# NMEA2000-FluidLevel.net
KiCad netlist of a schematic drawn in EAGLE
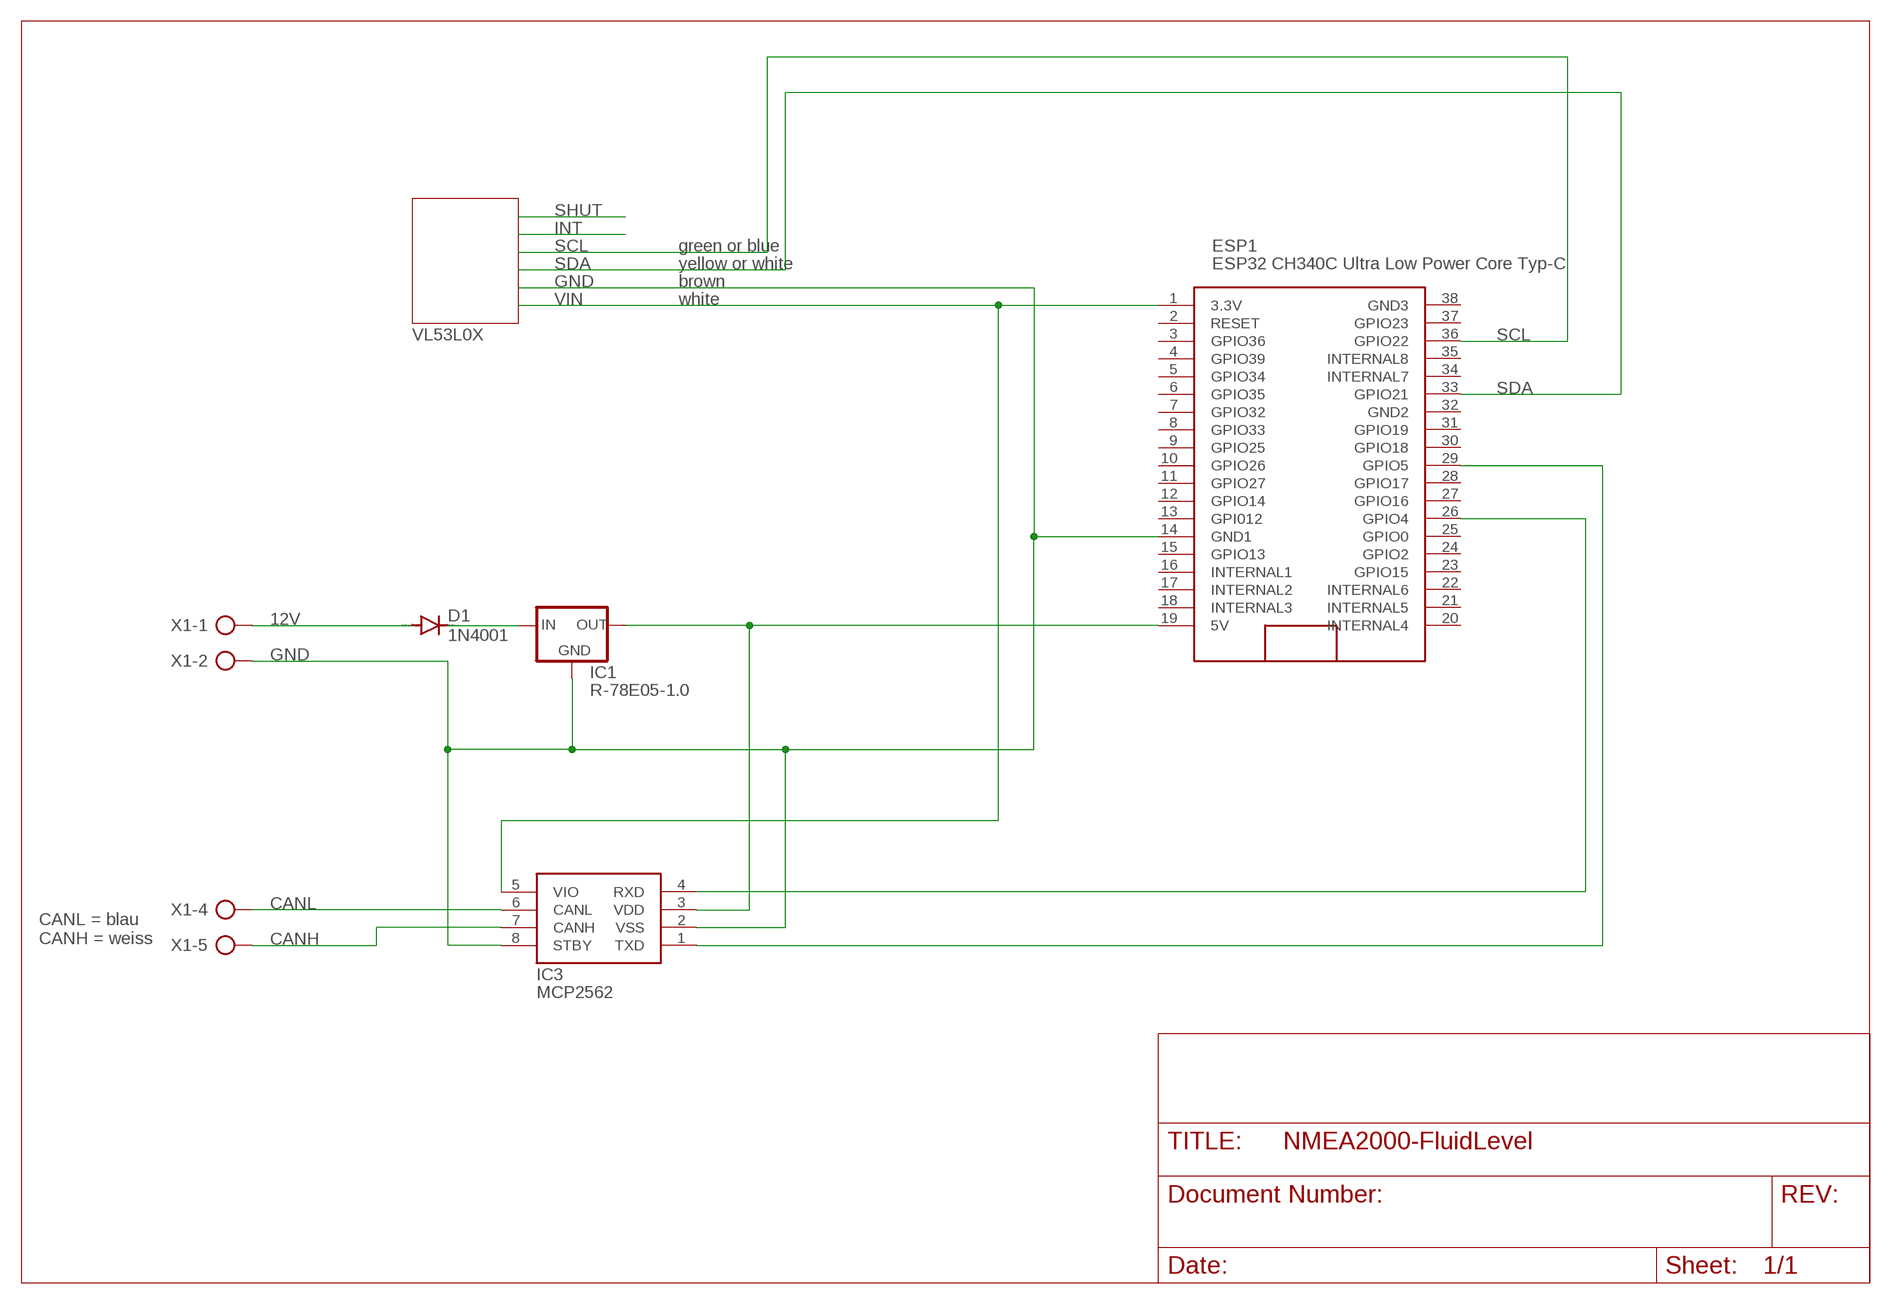
[diagram p0: schematic, sheet 1]

(export (version "E")
  (design (tool "Eeschema 10.0.6"))
  (components
    (comp (ref "D1")
      (value "1N4001")
      (footprint "eagle-import:DO41-10")
      (libsource (lib "eagle-import") (part "1N4004"))
    )
    (comp (ref "ESP1")
      (value "ESP32 CH340C Ultra Low Power Core Typ-C")
      (footprint "eagle-import:ESP32_NODEMCU")
      (libsource (lib "eagle-import") (part "ESP32-NODEMCU"))
    )
    (comp (ref "IC1")
      (value "R-78E05-1.0")
      (footprint "eagle-import:78XXS")
      (libsource (lib "eagle-import") (part "78XXS"))
    )
    (comp (ref "IC3")
      (value "MCP2562")
      (footprint "eagle-import:DIL08")
      (libsource (lib "eagle-import") (part "MCP2562"))
    )
    (comp (ref "X1")
      (value "AK500/5")
      (footprint "eagle-import:AK500_5")
      (libsource (lib "eagle-import") (part "AK500/5"))
    )
  )
  (nets
    (net (code "1") (name "/12V") (class "Default")
      (node (ref "D1") (pin "A") (pinfunction "A_A") (pintype "passive"))
      (node (ref "X1") (pin "1") (pinfunction "KL_1") (pintype "passive"))
    )
    (net (code "2") (name "/CANH") (class "Default")
      (node (ref "IC3") (pin "7") (pinfunction "CANH_7") (pintype "bidirectional"))
      (node (ref "X1") (pin "5") (pinfunction "KL_5") (pintype "passive"))
    )
    (net (code "3") (name "/CANL") (class "Default")
      (node (ref "IC3") (pin "6") (pinfunction "CANL_6") (pintype "bidirectional"))
      (node (ref "X1") (pin "4") (pinfunction "KL_4") (pintype "passive"))
    )
    (net (code "4") (name "/GND") (class "Default")
      (node (ref "ESP1") (pin "14") (pinfunction "GND1_14") (pintype "power_in"))
      (node (ref "IC1") (pin "GND") (pinfunction "GND_GND") (pintype "input"))
      (node (ref "IC3") (pin "2") (pinfunction "VSS_2") (pintype "bidirectional"))
      (node (ref "IC3") (pin "8") (pinfunction "STBY_8") (pintype "bidirectional"))
      (node (ref "X1") (pin "2") (pinfunction "KL_2") (pintype "passive"))
    )
    (net (code "5") (name "/GND2") (class "Default")
      (node (ref "ESP1") (pin "32") (pinfunction "GND2_32") (pintype "power_in"))
    )
    (net (code "6") (name "/GND3") (class "Default")
      (node (ref "ESP1") (pin "38") (pinfunction "GND3_38") (pintype "power_in"))
    )
    (net (code "8") (name "/SCL") (class "Default")
      (node (ref "ESP1") (pin "36") (pinfunction "GPIO22_36") (pintype "bidirectional"))
    )
    (net (code "9") (name "/SDA") (class "Default")
      (node (ref "ESP1") (pin "33") (pinfunction "GPIO21_33") (pintype "bidirectional"))
    )
    (net (code "11") (name "/VIN") (class "Default")
      (node (ref "ESP1") (pin "1") (pinfunction "3.3V_1") (pintype "power_in"))
      (node (ref "IC3") (pin "5") (pinfunction "VIO_5") (pintype "bidirectional"))
    )
    (net (code "12") (name "Net-(D1-PadC)") (class "Default")
      (node (ref "D1") (pin "C") (pinfunction "C_C") (pintype "passive"))
      (node (ref "IC1") (pin "IN") (pinfunction "IN_IN") (pintype "input"))
    )
    (net (code "13") (name "Net-(ESP1-5V)") (class "Default")
      (node (ref "ESP1") (pin "19") (pinfunction "5V_19") (pintype "power_in"))
      (node (ref "IC1") (pin "OUT") (pinfunction "OUT_OUT") (pintype "passive"))
      (node (ref "IC3") (pin "3") (pinfunction "VDD_3") (pintype "bidirectional"))
    )
    (net (code "14") (name "Net-(ESP1-GPIO4)") (class "Default")
      (node (ref "ESP1") (pin "26") (pinfunction "GPIO4_26") (pintype "bidirectional"))
      (node (ref "IC3") (pin "4") (pinfunction "RXD_4") (pintype "bidirectional"))
    )
    (net (code "15") (name "Net-(ESP1-GPIO5)") (class "Default")
      (node (ref "ESP1") (pin "29") (pinfunction "GPIO5_29") (pintype "bidirectional"))
      (node (ref "IC3") (pin "1") (pinfunction "TXD_1") (pintype "bidirectional"))
    )
    (net (code "16") (name "unconnected-(ESP1-GPI012-Pad13)") (class "Default")
      (node (ref "ESP1") (pin "13") (pinfunction "GPI012_13") (pintype "bidirectional"))
    )
    (net (code "17") (name "unconnected-(ESP1-GPIO0-Pad25)") (class "Default")
      (node (ref "ESP1") (pin "25") (pinfunction "GPIO0_25") (pintype "output"))
    )
    (net (code "18") (name "unconnected-(ESP1-GPIO2-Pad24)") (class "Default")
      (node (ref "ESP1") (pin "24") (pinfunction "GPIO2_24") (pintype "bidirectional"))
    )
    (net (code "19") (name "unconnected-(ESP1-GPIO13-Pad15)") (class "Default")
      (node (ref "ESP1") (pin "15") (pinfunction "GPIO13_15") (pintype "bidirectional"))
    )
    (net (code "20") (name "unconnected-(ESP1-GPIO14-Pad12)") (class "Default")
      (node (ref "ESP1") (pin "12") (pinfunction "GPIO14_12") (pintype "bidirectional"))
    )
    (net (code "21") (name "unconnected-(ESP1-GPIO15-Pad23)") (class "Default")
      (node (ref "ESP1") (pin "23") (pinfunction "GPIO15_23") (pintype "bidirectional"))
    )
    (net (code "22") (name "unconnected-(ESP1-GPIO16-Pad27)") (class "Default")
      (node (ref "ESP1") (pin "27") (pinfunction "GPIO16_27") (pintype "bidirectional"))
    )
    (net (code "23") (name "unconnected-(ESP1-GPIO17-Pad28)") (class "Default")
      (node (ref "ESP1") (pin "28") (pinfunction "GPIO17_28") (pintype "bidirectional"))
    )
    (net (code "24") (name "unconnected-(ESP1-GPIO18-Pad30)") (class "Default")
      (node (ref "ESP1") (pin "30") (pinfunction "GPIO18_30") (pintype "bidirectional"))
    )
    (net (code "25") (name "unconnected-(ESP1-GPIO19-Pad31)") (class "Default")
      (node (ref "ESP1") (pin "31") (pinfunction "GPIO19_31") (pintype "bidirectional"))
    )
    (net (code "26") (name "unconnected-(ESP1-GPIO23-Pad37)") (class "Default")
      (node (ref "ESP1") (pin "37") (pinfunction "GPIO23_37") (pintype "bidirectional"))
    )
    (net (code "27") (name "unconnected-(ESP1-GPIO25-Pad9)") (class "Default")
      (node (ref "ESP1") (pin "9") (pinfunction "GPIO25_9") (pintype "bidirectional"))
    )
    (net (code "28") (name "unconnected-(ESP1-GPIO26-Pad10)") (class "Default")
      (node (ref "ESP1") (pin "10") (pinfunction "GPIO26_10") (pintype "bidirectional"))
    )
    (net (code "29") (name "unconnected-(ESP1-GPIO27-Pad11)") (class "Default")
      (node (ref "ESP1") (pin "11") (pinfunction "GPIO27_11") (pintype "bidirectional"))
    )
    (net (code "30") (name "unconnected-(ESP1-GPIO32-Pad7)") (class "Default")
      (node (ref "ESP1") (pin "7") (pinfunction "GPIO32_7") (pintype "bidirectional"))
    )
    (net (code "31") (name "unconnected-(ESP1-GPIO33-Pad8)") (class "Default")
      (node (ref "ESP1") (pin "8") (pinfunction "GPIO33_8") (pintype "bidirectional"))
    )
    (net (code "32") (name "unconnected-(ESP1-GPIO34-Pad5)") (class "Default")
      (node (ref "ESP1") (pin "5") (pinfunction "GPIO34_5") (pintype "input"))
    )
    (net (code "33") (name "unconnected-(ESP1-GPIO35-Pad6)") (class "Default")
      (node (ref "ESP1") (pin "6") (pinfunction "GPIO35_6") (pintype "input"))
    )
    (net (code "34") (name "unconnected-(ESP1-GPIO36-Pad3)") (class "Default")
      (node (ref "ESP1") (pin "3") (pinfunction "GPIO36_3") (pintype "input"))
    )
    (net (code "35") (name "unconnected-(ESP1-GPIO39-Pad4)") (class "Default")
      (node (ref "ESP1") (pin "4") (pinfunction "GPIO39_4") (pintype "input"))
    )
    (net (code "36") (name "unconnected-(ESP1-INTERNAL1-Pad16)") (class "Default")
      (node (ref "ESP1") (pin "16") (pinfunction "INTERNAL1_16") (pintype "no_connect"))
    )
    (net (code "37") (name "unconnected-(ESP1-INTERNAL2-Pad17)") (class "Default")
      (node (ref "ESP1") (pin "17") (pinfunction "INTERNAL2_17") (pintype "no_connect"))
    )
    (net (code "38") (name "unconnected-(ESP1-INTERNAL3-Pad18)") (class "Default")
      (node (ref "ESP1") (pin "18") (pinfunction "INTERNAL3_18") (pintype "no_connect"))
    )
    (net (code "39") (name "unconnected-(ESP1-INTERNAL4-Pad20)") (class "Default")
      (node (ref "ESP1") (pin "20") (pinfunction "INTERNAL4_20") (pintype "no_connect"))
    )
    (net (code "40") (name "unconnected-(ESP1-INTERNAL5-Pad21)") (class "Default")
      (node (ref "ESP1") (pin "21") (pinfunction "INTERNAL5_21") (pintype "no_connect"))
    )
    (net (code "41") (name "unconnected-(ESP1-INTERNAL6-Pad22)") (class "Default")
      (node (ref "ESP1") (pin "22") (pinfunction "INTERNAL6_22") (pintype "no_connect"))
    )
    (net (code "42") (name "unconnected-(ESP1-INTERNAL7-Pad34)") (class "Default")
      (node (ref "ESP1") (pin "34") (pinfunction "INTERNAL7_34") (pintype "no_connect"))
    )
    (net (code "43") (name "unconnected-(ESP1-INTERNAL8-Pad35)") (class "Default")
      (node (ref "ESP1") (pin "35") (pinfunction "INTERNAL8_35") (pintype "no_connect"))
    )
    (net (code "44") (name "unconnected-(ESP1-RESET-Pad2)") (class "Default")
      (node (ref "ESP1") (pin "2") (pinfunction "RESET_2") (pintype "input"))
    )
  )
)
